# LTC4063-TestBoard_nicht_SMD.net
KiCad netlist of a schematic drawn in EAGLE
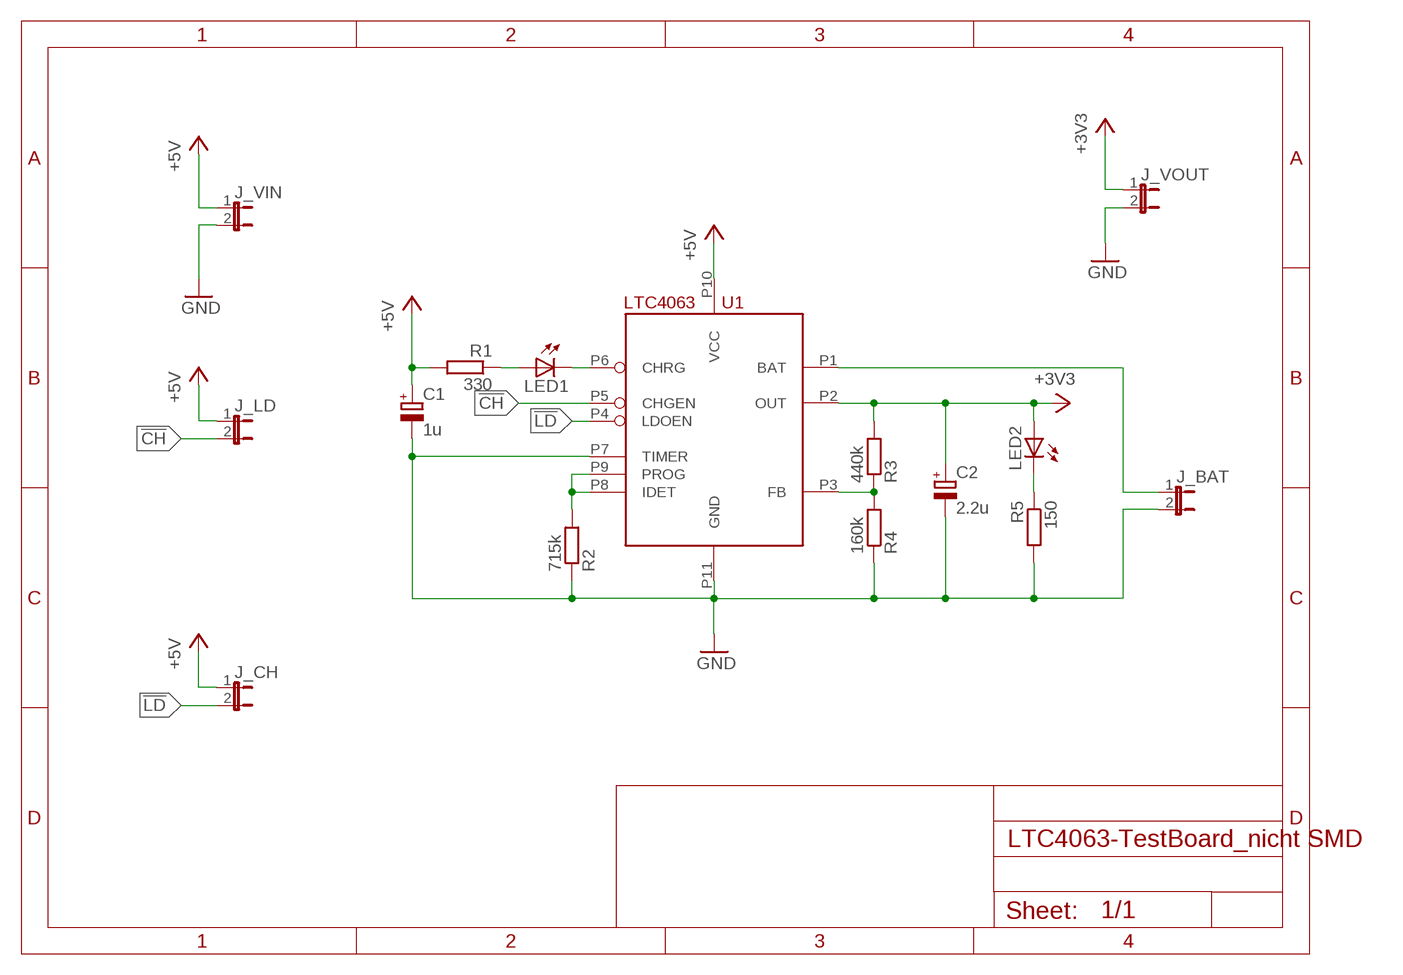
[diagram p0: schematic, sheet 1]

(export (version "E")
  (design (tool "Eeschema 10.0.6"))
  (components
    (comp (ref "C1")
      (value "1u")
      (footprint "eagle-import:E2,5-6")
      (libsource (lib "eagle-import") (part "CPOL-EUE2.5-6"))
    )
    (comp (ref "C2")
      (value "2.2u")
      (footprint "eagle-import:E2,5-6")
      (libsource (lib "eagle-import") (part "CPOL-EUE2.5-6"))
    )
    (comp (ref "J_BAT")
      (value "JP1E")
      (footprint "eagle-import:JP1")
      (libsource (lib "eagle-import") (part "JP1E"))
    )
    (comp (ref "J_CH")
      (value "JP1E")
      (footprint "eagle-import:JP1")
      (libsource (lib "eagle-import") (part "JP1E"))
    )
    (comp (ref "J_LD")
      (value "JP1E")
      (footprint "eagle-import:JP1")
      (libsource (lib "eagle-import") (part "JP1E"))
    )
    (comp (ref "J_VIN")
      (value "JP1E")
      (footprint "eagle-import:JP1")
      (libsource (lib "eagle-import") (part "JP1E"))
    )
    (comp (ref "J_VOUT")
      (value "JP1E")
      (footprint "eagle-import:JP1")
      (libsource (lib "eagle-import") (part "JP1E"))
    )
    (comp (ref "LED1")
      (value "LED3MM")
      (footprint "eagle-import:LED3MM")
      (libsource (lib "eagle-import") (part "LED3MM"))
    )
    (comp (ref "LED2")
      (value "LED3MM")
      (footprint "eagle-import:LED3MM")
      (libsource (lib "eagle-import") (part "LED3MM"))
    )
    (comp (ref "R1")
      (value "330")
      (footprint "eagle-import:0207_7")
      (libsource (lib "eagle-import") (part "R-EU_0207/7"))
    )
    (comp (ref "R2")
      (value "715k")
      (footprint "eagle-import:0207_7")
      (libsource (lib "eagle-import") (part "R-EU_0207/7"))
    )
    (comp (ref "R3")
      (value "440k")
      (footprint "eagle-import:0207_7")
      (libsource (lib "eagle-import") (part "R-EU_0207/7"))
    )
    (comp (ref "R4")
      (value "160k")
      (footprint "eagle-import:0207_7")
      (libsource (lib "eagle-import") (part "R-EU_0207/7"))
    )
    (comp (ref "R5")
      (value "150")
      (footprint "eagle-import:0207_7")
      (libsource (lib "eagle-import") (part "R-EU_0207/7"))
    )
    (comp (ref "U1")
      (value "LTC4063")
      (footprint "eagle-import:LTC4063")
      (libsource (lib "eagle-import") (part "LTC4063"))
    )
  )
  (nets
    (net (code "1") (name "+3V3") (class "Default")
      (node (ref "C2") (pin "+") (pinfunction "+_+") (pintype "passive"))
      (node (ref "J_VOUT") (pin "1") (pinfunction "1_1") (pintype "passive"))
      (node (ref "LED2") (pin "A") (pinfunction "A_A") (pintype "passive"))
      (node (ref "R3") (pin "2") (pinfunction "2_2") (pintype "passive"))
      (node (ref "U1") (pin "P2") (pinfunction "OUT_P2") (pintype "output"))
    )
    (net (code "2") (name "+5V") (class "Default")
      (node (ref "C1") (pin "+") (pinfunction "+_+") (pintype "passive"))
      (node (ref "J_CH") (pin "1") (pinfunction "1_1") (pintype "passive"))
      (node (ref "J_LD") (pin "1") (pinfunction "1_1") (pintype "passive"))
      (node (ref "J_VIN") (pin "1") (pinfunction "1_1") (pintype "passive"))
      (node (ref "R1") (pin "2") (pinfunction "2_2") (pintype "passive"))
      (node (ref "U1") (pin "P10") (pinfunction "VCC_P10") (pintype "power_in"))
    )
    (net (code "3") (name "/~{CH}") (class "Default")
      (node (ref "J_LD") (pin "2") (pinfunction "2_2") (pintype "passive"))
      (node (ref "U1") (pin "P5") (pinfunction "CHGEN_P5") (pintype "input"))
    )
    (net (code "4") (name "/~{LD}") (class "Default")
      (node (ref "J_CH") (pin "2") (pinfunction "2_2") (pintype "passive"))
      (node (ref "U1") (pin "P4") (pinfunction "LDOEN_P4") (pintype "input"))
    )
    (net (code "5") (name "GND") (class "Default")
      (node (ref "C1") (pin "-") (pinfunction "-_-") (pintype "passive"))
      (node (ref "C2") (pin "-") (pinfunction "-_-") (pintype "passive"))
      (node (ref "J_BAT") (pin "2") (pinfunction "2_2") (pintype "passive"))
      (node (ref "J_VIN") (pin "2") (pinfunction "2_2") (pintype "passive"))
      (node (ref "J_VOUT") (pin "2") (pinfunction "2_2") (pintype "passive"))
      (node (ref "R2") (pin "1") (pinfunction "1_1") (pintype "passive"))
      (node (ref "R4") (pin "1") (pinfunction "1_1") (pintype "passive"))
      (node (ref "R5") (pin "2") (pinfunction "2_2") (pintype "passive"))
      (node (ref "U1") (pin "P11") (pinfunction "GND_P11") (pintype "power_in"))
      (node (ref "U1") (pin "P7") (pinfunction "TIMER_P7") (pintype "passive"))
    )
    (net (code "6") (name "Net-(LED1-C)") (class "Default")
      (node (ref "LED1") (pin "K") (pinfunction "C_K") (pintype "passive"))
      (node (ref "U1") (pin "P6") (pinfunction "CHRG_P6") (pintype "output"))
    )
    (net (code "7") (name "Net-(LED1-PadA)") (class "Default")
      (node (ref "LED1") (pin "A") (pinfunction "A_A") (pintype "passive"))
      (node (ref "R1") (pin "1") (pinfunction "1_1") (pintype "passive"))
    )
    (net (code "8") (name "Net-(LED2-C)") (class "Default")
      (node (ref "LED2") (pin "K") (pinfunction "C_K") (pintype "passive"))
      (node (ref "R5") (pin "1") (pinfunction "1_1") (pintype "passive"))
    )
    (net (code "9") (name "Net-(U1-BAT)") (class "Default")
      (node (ref "J_BAT") (pin "1") (pinfunction "1_1") (pintype "passive"))
      (node (ref "U1") (pin "P1") (pinfunction "BAT_P1") (pintype "output"))
    )
    (net (code "10") (name "Net-(U1-FB)") (class "Default")
      (node (ref "R3") (pin "1") (pinfunction "1_1") (pintype "passive"))
      (node (ref "R4") (pin "2") (pinfunction "2_2") (pintype "passive"))
      (node (ref "U1") (pin "P3") (pinfunction "FB_P3") (pintype "passive"))
    )
    (net (code "11") (name "Net-(U1-IDET)") (class "Default")
      (node (ref "R2") (pin "2") (pinfunction "2_2") (pintype "passive"))
      (node (ref "U1") (pin "P8") (pinfunction "IDET_P8") (pintype "passive"))
      (node (ref "U1") (pin "P9") (pinfunction "PROG_P9") (pintype "passive"))
    )
  )
)
